# AUDIO_AMP_LM4849.net
KiCad netlist of a schematic drawn in Altium Designer
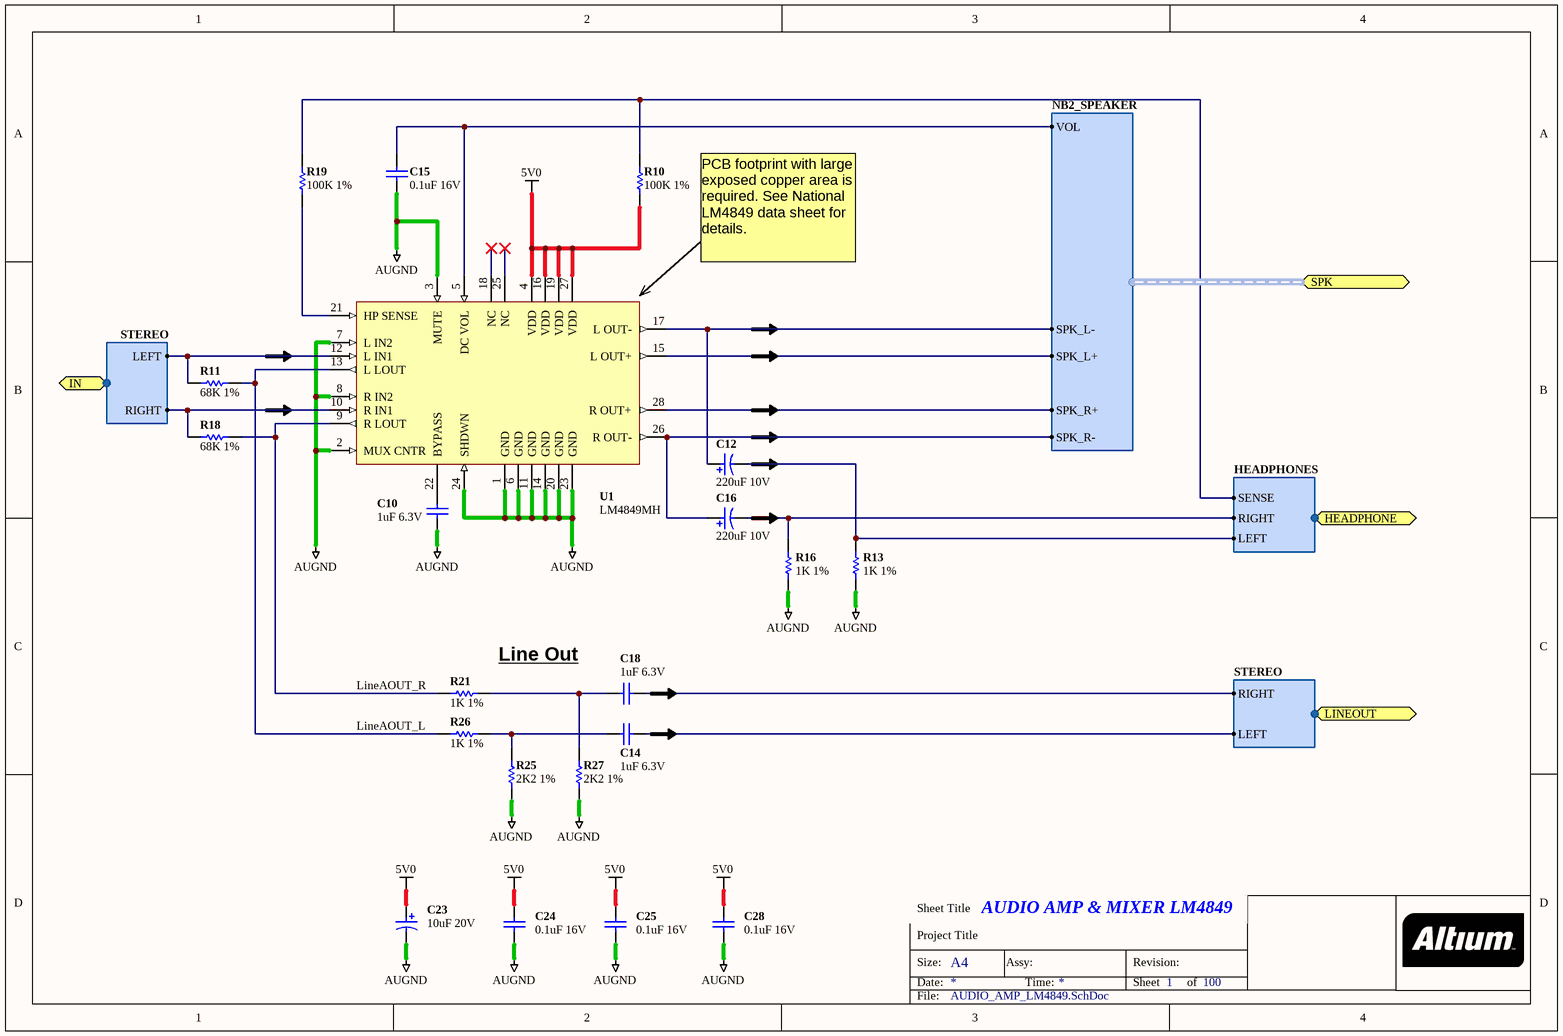
[diagram p0: AUDIO_AMP_LM4849.SchDoc]

(export (version "E")
  (design (tool "Eeschema 10.0.6"))
  (components
    (comp (ref "C10")
      (value "1uF 6.3V")
      (footprint "CAPC1005-STAR")
      (description "Capacitor, Ceramic, 1uF 10% 6.3V 0402 (1005) X5R")
      (fields (field (name "TOLERANCE") "10 %"))
      (libsource (lib "altium-import") (part "root_0_CAP-NP_"))
    )
    (comp (ref "C12")
      (value "220uF 10V")
      (footprint "CAPC7343-STAR")
      (description "Capacitor, Tantalum, 220uF 10% 10V MCCT-D (7343-31)")
      (fields (field (name "TOLERANCE") "10 %"))
      (libsource (lib "altium-import") (part "root_1_CAP-P_"))
    )
    (comp (ref "C14")
      (value "1uF 6.3V")
      (footprint "CAPC1005-STAR")
      (description "Capacitor, Ceramic, 1uF 10% 6.3V 0402 (1005) X5R")
      (fields (field (name "TOLERANCE") "10 %"))
      (libsource (lib "altium-import") (part "root_1_CAP-NP_"))
    )
    (comp (ref "C15")
      (value "0.1uF 16V")
      (footprint "CAPC1005-STAR")
      (description "Capacitor, Ceramic, 0.1uF 10% 16V 0402 (1005) X7R")
      (fields (field (name "TOLERANCE") "10 %"))
      (libsource (lib "altium-import") (part "root_2_CAP-NP_"))
    )
    (comp (ref "C16")
      (value "220uF 10V")
      (footprint "CAPC7343-STAR")
      (description "Capacitor, Tantalum, 220uF 10% 10V MCCT-D (7343-31)")
      (fields (field (name "TOLERANCE") "10 %"))
      (libsource (lib "altium-import") (part "root_1_CAP-P_"))
    )
    (comp (ref "C18")
      (value "1uF 6.3V")
      (footprint "CAPC1005-STAR")
      (description "Capacitor, Ceramic, 1uF 10% 6.3V 0402 (1005) X5R")
      (fields (field (name "TOLERANCE") "10 %"))
      (libsource (lib "altium-import") (part "root_3_CAP-NP_"))
    )
    (comp (ref "C23")
      (value "10uF 20V")
      (footprint "CAPC3528-STAR")
      (description "Capacitor, Tantalum, 10uF 10% 20V MCCT-B (3528)")
      (fields (field (name "TOLERANCE") "10 %"))
      (libsource (lib "altium-import") (part "root_0_mirrored_CAP-P_"))
    )
    (comp (ref "C24")
      (value "0.1uF 16V")
      (footprint "CAPC1005-STAR")
      (description "Capacitor, Ceramic, 0.1uF 10% 16V 0402 (1005) X7R")
      (fields (field (name "TOLERANCE") "10 %"))
      (libsource (lib "altium-import") (part "root_2_CAP-NP_"))
    )
    (comp (ref "C25")
      (value "0.1uF 16V")
      (footprint "CAPC1005-STAR")
      (description "Capacitor, Ceramic, 0.1uF 10% 16V 0402 (1005) X7R")
      (fields (field (name "TOLERANCE") "10 %"))
      (libsource (lib "altium-import") (part "root_2_CAP-NP_"))
    )
    (comp (ref "C28")
      (value "0.1uF 16V")
      (footprint "CAPC1005-STAR")
      (description "Capacitor, Ceramic, 0.1uF 10% 16V 0402 (1005) X7R")
      (fields (field (name "TOLERANCE") "10 %"))
      (libsource (lib "altium-import") (part "root_2_CAP-NP_"))
    )
    (comp (ref "R10")
      (value "100K 1%")
      (footprint "RESC1005-STAR")
      (description "Resistor, 100K 1% 0402 (1005)")
      (fields (field (name "TOLERANCE") "1 %"))
      (libsource (lib "altium-import") (part "root_0_RES_"))
    )
    (comp (ref "R11")
      (value "68K 1%")
      (footprint "RESC1005-STAR")
      (description "Resistor, 68K 1% 0402 (1005)")
      (fields (field (name "TOLERANCE") "1 %"))
      (libsource (lib "altium-import") (part "root_1_RES_"))
    )
    (comp (ref "R13")
      (value "1K 1%")
      (footprint "RESC1005-STAR")
      (description "Resistor, 1K 1% 0402 (1005)")
      (fields (field (name "TOLERANCE") "1 %"))
      (libsource (lib "altium-import") (part "root_2_RES_"))
    )
    (comp (ref "R16")
      (value "1K 1%")
      (footprint "RESC1005-STAR")
      (description "Resistor, 1K 1% 0402 (1005)")
      (fields (field (name "TOLERANCE") "1 %"))
      (libsource (lib "altium-import") (part "root_2_RES_"))
    )
    (comp (ref "R18")
      (value "68K 1%")
      (footprint "RESC1005-STAR")
      (description "Resistor, 68K 1% 0402 (1005)")
      (fields (field (name "TOLERANCE") "1 %"))
      (libsource (lib "altium-import") (part "root_1_RES_"))
    )
    (comp (ref "R19")
      (value "100K 1%")
      (footprint "RESC1005-STAR")
      (description "Resistor, 100K 1% 0402 (1005)")
      (fields (field (name "TOLERANCE") "1 %"))
      (libsource (lib "altium-import") (part "root_0_RES_"))
    )
    (comp (ref "R21")
      (value "1K 1%")
      (footprint "RESC1005-STAR")
      (description "Resistor, 1K 1% 0402 (1005)")
      (fields (field (name "TOLERANCE") "1 %"))
      (libsource (lib "altium-import") (part "root_1_RES_"))
    )
    (comp (ref "R25")
      (value "2K2 1%")
      (footprint "RESC1005-STAR")
      (description "Resistor, 2K2 1% 0402 (1005)")
      (fields (field (name "TOLERANCE") "1 %"))
      (libsource (lib "altium-import") (part "root_2_RES_"))
    )
    (comp (ref "R26")
      (value "1K 1%")
      (footprint "RESC1005-STAR")
      (description "Resistor, 1K 1% 0402 (1005)")
      (fields (field (name "TOLERANCE") "1 %"))
      (libsource (lib "altium-import") (part "root_1_RES_"))
    )
    (comp (ref "R27")
      (value "2K2 1%")
      (footprint "RESC1005-STAR")
      (description "Resistor, 2K2 1% 0402 (1005)")
      (fields (field (name "TOLERANCE") "1 %"))
      (libsource (lib "altium-import") (part "root_0_RES_"))
    )
    (comp (ref "U1")
      (value "LM4849MH")
      (footprint "TSOP65P640_HS-28")
      (description "LM4849MH Stereo 2W Audio Power Amplifier with DC Volume Control and Input Mux")
      (libsource (lib "altium-import") (part "root_0_LM4849_"))
    )
  )
  (nets
    (net (code "4") (name "/LineAOUT_L") (class "Default")
      (node (ref "R11") (pin "2") (pinfunction "2_2") (pintype "passive"))
      (node (ref "R26") (pin "1") (pinfunction "1_1") (pintype "passive"))
      (node (ref "U1") (pin "13") (pinfunction "L_LOUT_13") (pintype "output"))
    )
    (net (code "5") (name "/LineAOUT_R") (class "Default")
      (node (ref "R18") (pin "2") (pinfunction "2_2") (pintype "passive"))
      (node (ref "R21") (pin "1") (pinfunction "1_1") (pintype "passive"))
      (node (ref "U1") (pin "9") (pinfunction "R_LOUT_9") (pintype "output"))
    )
    (net (code "6") (name "/SENSE") (class "Default")
      (node (ref "R10") (pin "1") (pinfunction "1_1") (pintype "passive"))
      (node (ref "R19") (pin "1") (pinfunction "1_1") (pintype "passive"))
    )
    (net (code "7") (name "/SPK_L+") (class "Default")
      (node (ref "U1") (pin "15") (pinfunction "L_OUT+_15") (pintype "output"))
    )
    (net (code "8") (name "/SPK_L-") (class "Default")
      (node (ref "C12") (pin "1") (pinfunction "1_1") (pintype "passive"))
      (node (ref "U1") (pin "17") (pinfunction "L_OUT-_17") (pintype "output"))
    )
    (net (code "9") (name "/SPK_R+") (class "Default")
      (node (ref "U1") (pin "28") (pinfunction "R_OUT+_28") (pintype "output"))
    )
    (net (code "10") (name "/SPK_R-") (class "Default")
      (node (ref "C16") (pin "1") (pinfunction "1_1") (pintype "passive"))
      (node (ref "U1") (pin "26") (pinfunction "R_OUT-_26") (pintype "output"))
    )
    (net (code "11") (name "/VOL") (class "Default")
      (node (ref "C15") (pin "2") (pinfunction "2_2") (pintype "passive"))
      (node (ref "U1") (pin "5") (pinfunction "DC_VOL_5") (pintype "input"))
    )
    (net (code "15") (name "5V0") (class "Default")
      (node (ref "C23") (pin "1") (pinfunction "1_1") (pintype "passive"))
      (node (ref "C24") (pin "2") (pinfunction "2_2") (pintype "passive"))
      (node (ref "C25") (pin "2") (pinfunction "2_2") (pintype "passive"))
      (node (ref "C28") (pin "2") (pinfunction "2_2") (pintype "passive"))
      (node (ref "R10") (pin "2") (pinfunction "2_2") (pintype "passive"))
      (node (ref "U1") (pin "16") (pinfunction "VDD_16") (pintype "power_in"))
      (node (ref "U1") (pin "19") (pinfunction "VDD_19") (pintype "power_in"))
      (node (ref "U1") (pin "27") (pinfunction "VDD_27") (pintype "power_in"))
      (node (ref "U1") (pin "4") (pinfunction "VDD_4") (pintype "power_in"))
    )
    (net (code "16") (name "AUGND") (class "Default")
      (node (ref "C10") (pin "2") (pinfunction "2_2") (pintype "passive"))
      (node (ref "C15") (pin "1") (pinfunction "1_1") (pintype "passive"))
      (node (ref "C23") (pin "2") (pinfunction "2_2") (pintype "passive"))
      (node (ref "C24") (pin "1") (pinfunction "1_1") (pintype "passive"))
      (node (ref "C25") (pin "1") (pinfunction "1_1") (pintype "passive"))
      (node (ref "C28") (pin "1") (pinfunction "1_1") (pintype "passive"))
      (node (ref "R13") (pin "1") (pinfunction "1_1") (pintype "passive"))
      (node (ref "R16") (pin "1") (pinfunction "1_1") (pintype "passive"))
      (node (ref "R25") (pin "1") (pinfunction "1_1") (pintype "passive"))
      (node (ref "R27") (pin "2") (pinfunction "2_2") (pintype "passive"))
      (node (ref "U1") (pin "1") (pinfunction "GND_1") (pintype "power_in"))
      (node (ref "U1") (pin "11") (pinfunction "GND_11") (pintype "power_in"))
      (node (ref "U1") (pin "14") (pinfunction "GND_14") (pintype "power_in"))
      (node (ref "U1") (pin "2") (pinfunction "MUX_CNTR_2") (pintype "input"))
      (node (ref "U1") (pin "20") (pinfunction "GND_20") (pintype "power_in"))
      (node (ref "U1") (pin "23") (pinfunction "GND_23") (pintype "power_in"))
      (node (ref "U1") (pin "24") (pinfunction "SHDWN_24") (pintype "input"))
      (node (ref "U1") (pin "3") (pinfunction "MUTE_3") (pintype "input"))
      (node (ref "U1") (pin "6") (pinfunction "GND_6") (pintype "power_in"))
      (node (ref "U1") (pin "7") (pinfunction "L_IN2_7") (pintype "input"))
      (node (ref "U1") (pin "8") (pinfunction "R_IN2_8") (pintype "input"))
    )
    (net (code "17") (name "Net-(C12-Pad2)") (class "Default")
      (node (ref "C12") (pin "2") (pinfunction "2_2") (pintype "passive"))
      (node (ref "R13") (pin "2") (pinfunction "2_2") (pintype "passive"))
    )
    (net (code "18") (name "Net-(C14-Pad1)") (class "Default")
      (node (ref "C14") (pin "1") (pinfunction "1_1") (pintype "passive"))
      (node (ref "R25") (pin "2") (pinfunction "2_2") (pintype "passive"))
      (node (ref "R26") (pin "2") (pinfunction "2_2") (pintype "passive"))
    )
    (net (code "19") (name "Net-(C16-Pad2)") (class "Default")
      (node (ref "C16") (pin "2") (pinfunction "2_2") (pintype "passive"))
      (node (ref "R16") (pin "2") (pinfunction "2_2") (pintype "passive"))
    )
    (net (code "20") (name "Net-(C18-Pad2)") (class "Default")
      (node (ref "C18") (pin "2") (pinfunction "2_2") (pintype "passive"))
      (node (ref "R21") (pin "2") (pinfunction "2_2") (pintype "passive"))
      (node (ref "R27") (pin "1") (pinfunction "1_1") (pintype "passive"))
    )
    (net (code "21") (name "Net-(U1-BYPASS)") (class "Default")
      (node (ref "C10") (pin "1") (pinfunction "1_1") (pintype "passive"))
      (node (ref "U1") (pin "22") (pinfunction "BYPASS_22") (pintype "passive"))
    )
    (net (code "22") (name "Net-(U1-HP_SENSE)") (class "Default")
      (node (ref "R19") (pin "2") (pinfunction "2_2") (pintype "passive"))
      (node (ref "U1") (pin "21") (pinfunction "HP_SENSE_21") (pintype "input"))
    )
    (net (code "23") (name "Net-(U1-L_IN1)") (class "Default")
      (node (ref "R11") (pin "1") (pinfunction "1_1") (pintype "passive"))
      (node (ref "U1") (pin "12") (pinfunction "L_IN1_12") (pintype "input"))
    )
    (net (code "24") (name "Net-(U1-R_IN1)") (class "Default")
      (node (ref "R18") (pin "1") (pinfunction "1_1") (pintype "passive"))
      (node (ref "U1") (pin "10") (pinfunction "R_IN1_10") (pintype "input"))
    )
    (net (code "25") (name "unconnected-(C14-Pad2)") (class "Default")
      (node (ref "C14") (pin "2") (pinfunction "2_2") (pintype "passive"))
    )
    (net (code "26") (name "unconnected-(C18-Pad1)") (class "Default")
      (node (ref "C18") (pin "1") (pinfunction "1_1") (pintype "passive"))
    )
    (net (code "27") (name "unconnected-(U1-NC-Pad18)") (class "Default")
      (node (ref "U1") (pin "18") (pinfunction "NC_18") (pintype "passive+no_connect"))
    )
    (net (code "28") (name "unconnected-(U1-NC-Pad25)") (class "Default")
      (node (ref "U1") (pin "25") (pinfunction "NC_25") (pintype "passive+no_connect"))
    )
  )
)
